# PCB_Univ_V0.net
KiCad netlist of a schematic drawn in EAGLE
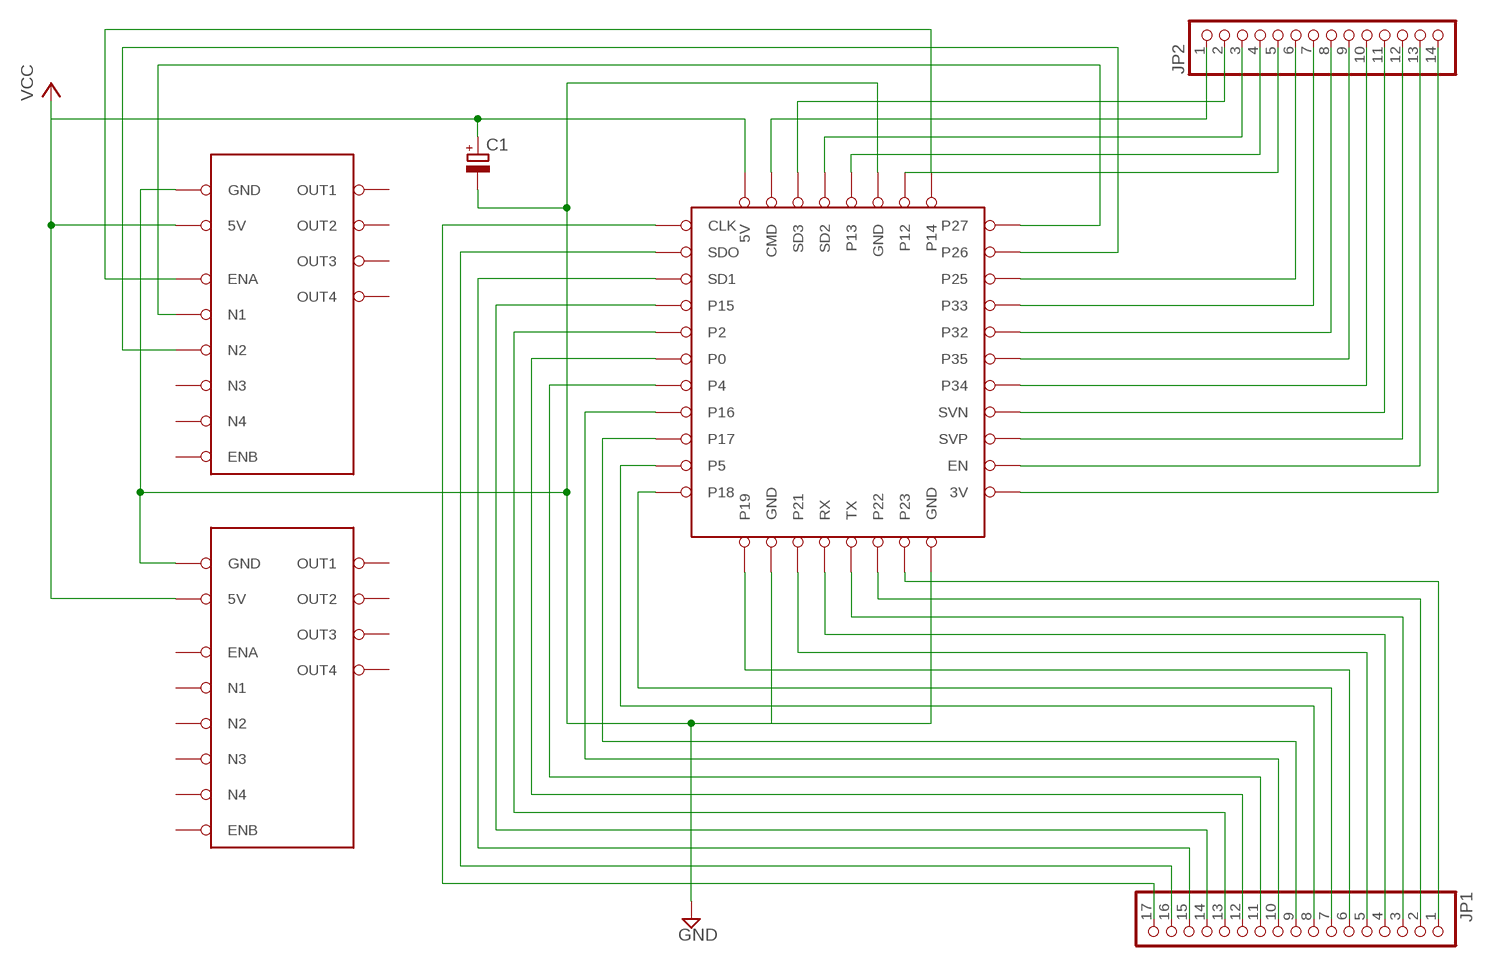
[diagram p0: schematic, sheet 1]

(export (version "E")
  (design (tool "Eeschema 10.0.6"))
  (components
    (comp (ref "C1")
      (value "CPOL-EUE3.5-8")
      (footprint "eagle-import:E3,5-8")
      (libsource (lib "eagle-import") (part "CPOL-EUE3.5-8"))
    )
    (comp (ref "ESP1")
      (value "ESP12_MOD")
      (footprint "eagle-import:ESP32_MOD")
      (libsource (lib "eagle-import") (part "ESP12_MOD"))
    )
    (comp (ref "JP1")
      (value "PINHD-1X17")
      (footprint "eagle-import:1X17")
      (libsource (lib "eagle-import") (part "PINHD-1X17"))
    )
    (comp (ref "JP2")
      (value "PINHD-1X14")
      (footprint "eagle-import:1X14")
      (libsource (lib "eagle-import") (part "PINHD-1X14"))
    )
    (comp (ref "U$1")
      (value "DRIVER_MOTOR")
      (footprint "eagle-import:DRIVER_MOTOR")
      (libsource (lib "eagle-import") (part "DRIVER_MOTOR"))
    )
    (comp (ref "U$2")
      (value "DRIVER_MOTOR")
      (footprint "eagle-import:DRIVER_MOTOR")
      (libsource (lib "eagle-import") (part "DRIVER_MOTOR"))
    )
  )
  (nets
    (net (code "1") (name "GND") (class "Default")
      (node (ref "C1") (pin "-") (pinfunction "-_-") (pintype "passive"))
      (node (ref "ESP1") (pin "P$13") (pinfunction "GND_P$13") (pintype "bidirectional"))
      (node (ref "ESP1") (pin "P$19") (pinfunction "GND_P$19") (pintype "bidirectional"))
      (node (ref "ESP1") (pin "P$33") (pinfunction "GND_P$33") (pintype "bidirectional"))
      (node (ref "U$1") (pin "GND") (pinfunction "GND_GND") (pintype "bidirectional"))
      (node (ref "U$2") (pin "GND") (pinfunction "GND_GND") (pintype "bidirectional"))
    )
    (net (code "2") (name "Net-(ESP1-3V)") (class "Default")
      (node (ref "ESP1") (pin "P$20") (pinfunction "3V_P$20") (pintype "bidirectional"))
      (node (ref "JP2") (pin "14") (pinfunction "14_14") (pintype "passive"))
    )
    (net (code "3") (name "Net-(ESP1-CLK)") (class "Default")
      (node (ref "ESP1") (pin "P$1") (pinfunction "CLK_P$1") (pintype "bidirectional"))
      (node (ref "JP1") (pin "17") (pinfunction "17_17") (pintype "passive"))
    )
    (net (code "4") (name "Net-(ESP1-CMD)") (class "Default")
      (node (ref "ESP1") (pin "P$37") (pinfunction "CMD_P$37") (pintype "bidirectional"))
      (node (ref "JP2") (pin "1") (pinfunction "1_1") (pintype "passive"))
    )
    (net (code "5") (name "Net-(ESP1-EN)") (class "Default")
      (node (ref "ESP1") (pin "P$21") (pinfunction "EN_P$21") (pintype "bidirectional"))
      (node (ref "JP2") (pin "13") (pinfunction "13_13") (pintype "passive"))
    )
    (net (code "6") (name "Net-(ESP1-P0)") (class "Default")
      (node (ref "ESP1") (pin "P$6") (pinfunction "P0_P$6") (pintype "bidirectional"))
      (node (ref "JP1") (pin "12") (pinfunction "12_12") (pintype "passive"))
    )
    (net (code "7") (name "Net-(ESP1-P2)") (class "Default")
      (node (ref "ESP1") (pin "P$5") (pinfunction "P2_P$5") (pintype "bidirectional"))
      (node (ref "JP1") (pin "13") (pinfunction "13_13") (pintype "passive"))
    )
    (net (code "8") (name "Net-(ESP1-P4)") (class "Default")
      (node (ref "ESP1") (pin "P$7") (pinfunction "P4_P$7") (pintype "bidirectional"))
      (node (ref "JP1") (pin "11") (pinfunction "11_11") (pintype "passive"))
    )
    (net (code "9") (name "Net-(ESP1-P5)") (class "Default")
      (node (ref "ESP1") (pin "P$10") (pinfunction "P5_P$10") (pintype "bidirectional"))
      (node (ref "JP1") (pin "8") (pinfunction "8_8") (pintype "passive"))
    )
    (net (code "10") (name "Net-(ESP1-P12)") (class "Default")
      (node (ref "ESP1") (pin "P$32") (pinfunction "P12_P$32") (pintype "bidirectional"))
      (node (ref "JP2") (pin "5") (pinfunction "5_5") (pintype "passive"))
    )
    (net (code "11") (name "Net-(ESP1-P13)") (class "Default")
      (node (ref "ESP1") (pin "P$34") (pinfunction "P13_P$34") (pintype "bidirectional"))
      (node (ref "JP2") (pin "4") (pinfunction "4_4") (pintype "passive"))
    )
    (net (code "12") (name "Net-(ESP1-P14)") (class "Default")
      (node (ref "ESP1") (pin "P$31") (pinfunction "P14_P$31") (pintype "bidirectional"))
      (node (ref "U$1") (pin "ENA") (pinfunction "ENA_ENA") (pintype "bidirectional"))
    )
    (net (code "13") (name "Net-(ESP1-P15)") (class "Default")
      (node (ref "ESP1") (pin "P$4") (pinfunction "P15_P$4") (pintype "bidirectional"))
      (node (ref "JP1") (pin "14") (pinfunction "14_14") (pintype "passive"))
    )
    (net (code "14") (name "Net-(ESP1-P16)") (class "Default")
      (node (ref "ESP1") (pin "P$8") (pinfunction "P16_P$8") (pintype "bidirectional"))
      (node (ref "JP1") (pin "10") (pinfunction "10_10") (pintype "passive"))
    )
    (net (code "15") (name "Net-(ESP1-P17)") (class "Default")
      (node (ref "ESP1") (pin "P$9") (pinfunction "P17_P$9") (pintype "bidirectional"))
      (node (ref "JP1") (pin "9") (pinfunction "9_9") (pintype "passive"))
    )
    (net (code "16") (name "Net-(ESP1-P18)") (class "Default")
      (node (ref "ESP1") (pin "P$11") (pinfunction "P18_P$11") (pintype "bidirectional"))
      (node (ref "JP1") (pin "7") (pinfunction "7_7") (pintype "passive"))
    )
    (net (code "17") (name "Net-(ESP1-P19)") (class "Default")
      (node (ref "ESP1") (pin "P$12") (pinfunction "P19_P$12") (pintype "bidirectional"))
      (node (ref "JP1") (pin "6") (pinfunction "6_6") (pintype "passive"))
    )
    (net (code "18") (name "Net-(ESP1-P21)") (class "Default")
      (node (ref "ESP1") (pin "P$14") (pinfunction "P21_P$14") (pintype "bidirectional"))
      (node (ref "JP1") (pin "5") (pinfunction "5_5") (pintype "passive"))
    )
    (net (code "19") (name "Net-(ESP1-P22)") (class "Default")
      (node (ref "ESP1") (pin "P$17") (pinfunction "P22_P$17") (pintype "bidirectional"))
      (node (ref "JP1") (pin "2") (pinfunction "2_2") (pintype "passive"))
    )
    (net (code "20") (name "Net-(ESP1-P23)") (class "Default")
      (node (ref "ESP1") (pin "P$18") (pinfunction "P23_P$18") (pintype "bidirectional"))
      (node (ref "JP1") (pin "1") (pinfunction "1_1") (pintype "passive"))
    )
    (net (code "21") (name "Net-(ESP1-P25)") (class "Default")
      (node (ref "ESP1") (pin "P$28") (pinfunction "P25_P$28") (pintype "bidirectional"))
      (node (ref "JP2") (pin "6") (pinfunction "6_6") (pintype "passive"))
    )
    (net (code "22") (name "Net-(ESP1-P26)") (class "Default")
      (node (ref "ESP1") (pin "P$29") (pinfunction "P26_P$29") (pintype "bidirectional"))
      (node (ref "U$1") (pin "N2") (pinfunction "N2_N2") (pintype "bidirectional"))
    )
    (net (code "23") (name "Net-(ESP1-P27)") (class "Default")
      (node (ref "ESP1") (pin "P$30") (pinfunction "P27_P$30") (pintype "bidirectional"))
      (node (ref "U$1") (pin "N1") (pinfunction "N1_N1") (pintype "bidirectional"))
    )
    (net (code "24") (name "Net-(ESP1-P32)") (class "Default")
      (node (ref "ESP1") (pin "P$26") (pinfunction "P32_P$26") (pintype "bidirectional"))
      (node (ref "JP2") (pin "8") (pinfunction "8_8") (pintype "passive"))
    )
    (net (code "25") (name "Net-(ESP1-P33)") (class "Default")
      (node (ref "ESP1") (pin "P$27") (pinfunction "P33_P$27") (pintype "bidirectional"))
      (node (ref "JP2") (pin "7") (pinfunction "7_7") (pintype "passive"))
    )
    (net (code "26") (name "Net-(ESP1-P34)") (class "Default")
      (node (ref "ESP1") (pin "P$24") (pinfunction "P34_P$24") (pintype "bidirectional"))
      (node (ref "JP2") (pin "10") (pinfunction "10_10") (pintype "passive"))
    )
    (net (code "27") (name "Net-(ESP1-P35)") (class "Default")
      (node (ref "ESP1") (pin "P$25") (pinfunction "P35_P$25") (pintype "bidirectional"))
      (node (ref "JP2") (pin "9") (pinfunction "9_9") (pintype "passive"))
    )
    (net (code "28") (name "Net-(ESP1-RX)") (class "Default")
      (node (ref "ESP1") (pin "P$15") (pinfunction "RX_P$15") (pintype "bidirectional"))
      (node (ref "JP1") (pin "4") (pinfunction "4_4") (pintype "passive"))
    )
    (net (code "29") (name "Net-(ESP1-SD1)") (class "Default")
      (node (ref "ESP1") (pin "P$3") (pinfunction "SD1_P$3") (pintype "bidirectional"))
      (node (ref "JP1") (pin "15") (pinfunction "15_15") (pintype "passive"))
    )
    (net (code "30") (name "Net-(ESP1-SD2)") (class "Default")
      (node (ref "ESP1") (pin "P$35") (pinfunction "SD2_P$35") (pintype "bidirectional"))
      (node (ref "JP2") (pin "3") (pinfunction "3_3") (pintype "passive"))
    )
    (net (code "31") (name "Net-(ESP1-SD3)") (class "Default")
      (node (ref "ESP1") (pin "P$36") (pinfunction "SD3_P$36") (pintype "bidirectional"))
      (node (ref "JP2") (pin "2") (pinfunction "2_2") (pintype "passive"))
    )
    (net (code "32") (name "Net-(ESP1-SDO)") (class "Default")
      (node (ref "ESP1") (pin "P$2") (pinfunction "SDO_P$2") (pintype "bidirectional"))
      (node (ref "JP1") (pin "16") (pinfunction "16_16") (pintype "passive"))
    )
    (net (code "33") (name "Net-(ESP1-SVN)") (class "Default")
      (node (ref "ESP1") (pin "P$23") (pinfunction "SVN_P$23") (pintype "bidirectional"))
      (node (ref "JP2") (pin "11") (pinfunction "11_11") (pintype "passive"))
    )
    (net (code "34") (name "Net-(ESP1-SVP)") (class "Default")
      (node (ref "ESP1") (pin "P$22") (pinfunction "SVP_P$22") (pintype "bidirectional"))
      (node (ref "JP2") (pin "12") (pinfunction "12_12") (pintype "passive"))
    )
    (net (code "35") (name "Net-(ESP1-TX)") (class "Default")
      (node (ref "ESP1") (pin "P$16") (pinfunction "TX_P$16") (pintype "bidirectional"))
      (node (ref "JP1") (pin "3") (pinfunction "3_3") (pintype "passive"))
    )
    (net (code "36") (name "VCC") (class "Default")
      (node (ref "C1") (pin "+") (pinfunction "+_+") (pintype "passive"))
      (node (ref "ESP1") (pin "P$38") (pinfunction "5V_P$38") (pintype "bidirectional"))
      (node (ref "U$1") (pin "5V") (pinfunction "5V_5V") (pintype "bidirectional"))
      (node (ref "U$2") (pin "5V") (pinfunction "5V_5V") (pintype "bidirectional"))
    )
    (net (code "37") (name "unconnected-(U$1-PadENB)") (class "Default")
      (node (ref "U$1") (pin "ENB") (pinfunction "ENB_ENB") (pintype "bidirectional"))
    )
    (net (code "38") (name "unconnected-(U$1-PadN3)") (class "Default")
      (node (ref "U$1") (pin "N3") (pinfunction "N3_N3") (pintype "bidirectional"))
    )
    (net (code "39") (name "unconnected-(U$1-PadN4)") (class "Default")
      (node (ref "U$1") (pin "N4") (pinfunction "N4_N4") (pintype "bidirectional"))
    )
    (net (code "40") (name "unconnected-(U$1-PadOUT1)") (class "Default")
      (node (ref "U$1") (pin "OUT1") (pinfunction "OUT1_OUT1") (pintype "bidirectional"))
    )
    (net (code "41") (name "unconnected-(U$1-PadOUT2)") (class "Default")
      (node (ref "U$1") (pin "OUT2") (pinfunction "OUT2_OUT2") (pintype "bidirectional"))
    )
    (net (code "42") (name "unconnected-(U$1-PadOUT3)") (class "Default")
      (node (ref "U$1") (pin "OUT3") (pinfunction "OUT3_OUT3") (pintype "bidirectional"))
    )
    (net (code "43") (name "unconnected-(U$1-PadOUT4)") (class "Default")
      (node (ref "U$1") (pin "OUT4") (pinfunction "OUT4_OUT4") (pintype "bidirectional"))
    )
    (net (code "44") (name "unconnected-(U$2-PadENA)") (class "Default")
      (node (ref "U$2") (pin "ENA") (pinfunction "ENA_ENA") (pintype "bidirectional"))
    )
    (net (code "45") (name "unconnected-(U$2-PadENB)") (class "Default")
      (node (ref "U$2") (pin "ENB") (pinfunction "ENB_ENB") (pintype "bidirectional"))
    )
    (net (code "46") (name "unconnected-(U$2-PadN1)") (class "Default")
      (node (ref "U$2") (pin "N1") (pinfunction "N1_N1") (pintype "bidirectional"))
    )
    (net (code "47") (name "unconnected-(U$2-PadN2)") (class "Default")
      (node (ref "U$2") (pin "N2") (pinfunction "N2_N2") (pintype "bidirectional"))
    )
    (net (code "48") (name "unconnected-(U$2-PadN3)") (class "Default")
      (node (ref "U$2") (pin "N3") (pinfunction "N3_N3") (pintype "bidirectional"))
    )
    (net (code "49") (name "unconnected-(U$2-PadN4)") (class "Default")
      (node (ref "U$2") (pin "N4") (pinfunction "N4_N4") (pintype "bidirectional"))
    )
    (net (code "50") (name "unconnected-(U$2-PadOUT1)") (class "Default")
      (node (ref "U$2") (pin "OUT1") (pinfunction "OUT1_OUT1") (pintype "bidirectional"))
    )
    (net (code "51") (name "unconnected-(U$2-PadOUT2)") (class "Default")
      (node (ref "U$2") (pin "OUT2") (pinfunction "OUT2_OUT2") (pintype "bidirectional"))
    )
    (net (code "52") (name "unconnected-(U$2-PadOUT3)") (class "Default")
      (node (ref "U$2") (pin "OUT3") (pinfunction "OUT3_OUT3") (pintype "bidirectional"))
    )
    (net (code "53") (name "unconnected-(U$2-PadOUT4)") (class "Default")
      (node (ref "U$2") (pin "OUT4") (pinfunction "OUT4_OUT4") (pintype "bidirectional"))
    )
  )
)
